# Close_eMuff.net
KiCad netlist of a schematic drawn in EAGLE
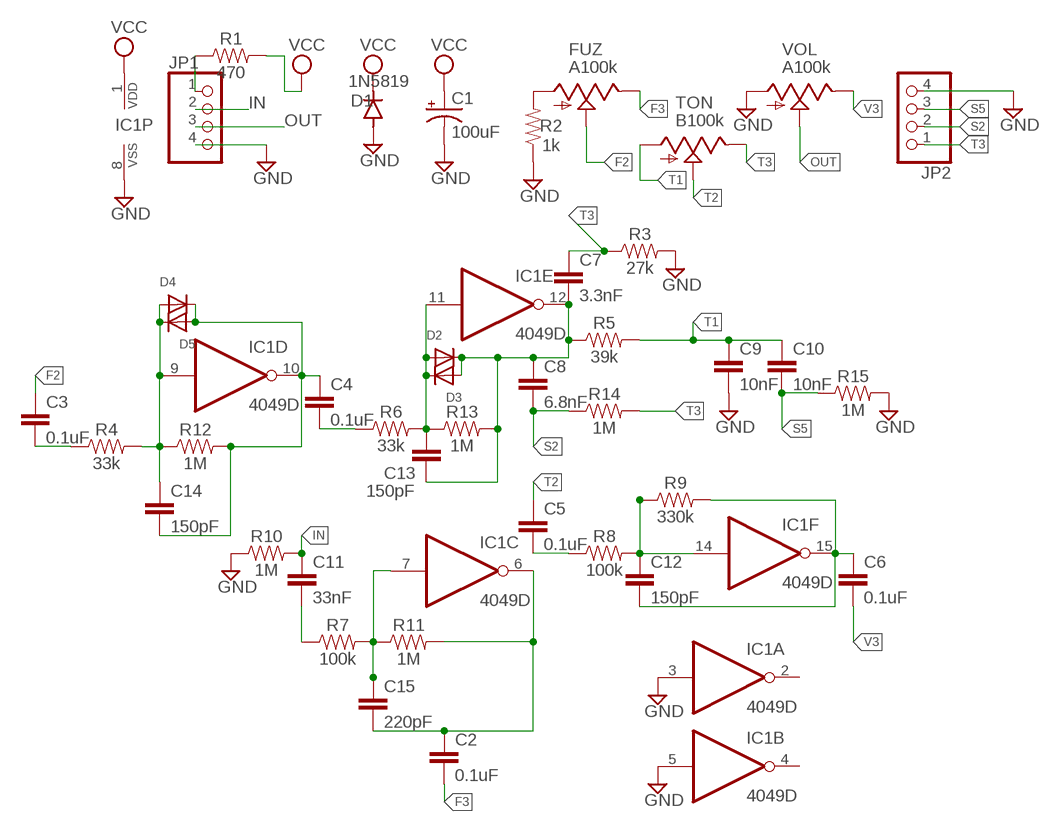
[diagram p0: schematic, sheet 1]

(export (version "E")
  (design (tool "Eeschema 10.0.6"))
  (components
    (comp (ref "C1")
      (value "100uF")
      (footprint "eagle-import:PAN_B_SMD+THRU")
      (libsource (lib "eagle-import") (part "CAP_SMD+THRUPAN_B"))
    )
    (comp (ref "C2")
      (value "0.1uF")
      (footprint "eagle-import:0603")
      (libsource (lib "eagle-import") (part "0.1UF-0603-25V-(+80/-20%)"))
    )
    (comp (ref "C3")
      (value "0.1uF")
      (footprint "eagle-import:0603")
      (libsource (lib "eagle-import") (part "0.1UF-0603-25V-(+80/-20%)"))
    )
    (comp (ref "C4")
      (value "0.1uF")
      (footprint "eagle-import:0603")
      (libsource (lib "eagle-import") (part "0.1UF-0603-25V-(+80/-20%)"))
    )
    (comp (ref "C5")
      (value "0.1uF")
      (footprint "eagle-import:0603")
      (libsource (lib "eagle-import") (part "0.1UF-0603-25V-(+80/-20%)"))
    )
    (comp (ref "C6")
      (value "0.1uF")
      (footprint "eagle-import:0603")
      (libsource (lib "eagle-import") (part "0.1UF-0603-25V-(+80/-20%)"))
    )
    (comp (ref "C7")
      (value "3.3nF")
      (footprint "eagle-import:0603")
      (libsource (lib "eagle-import") (part "3.3NF-0603-100V-10%"))
    )
    (comp (ref "C8")
      (value "6.8nF")
      (footprint "eagle-import:0603")
      (libsource (lib "eagle-import") (part "3.3NF-0603-100V-10%"))
    )
    (comp (ref "C9")
      (value "10nF")
      (footprint "eagle-import:0603")
      (libsource (lib "eagle-import") (part "10NF-0603-50V-10%"))
    )
    (comp (ref "C10")
      (value "10nF")
      (footprint "eagle-import:0603")
      (libsource (lib "eagle-import") (part "10NF-0603-50V-10%"))
    )
    (comp (ref "C11")
      (value "33nF")
      (footprint "eagle-import:0603")
      (libsource (lib "eagle-import") (part "33PF-0603-50V-5%"))
    )
    (comp (ref "C12")
      (value "150pF")
      (footprint "eagle-import:0603")
      (libsource (lib "eagle-import") (part "180PF-0603-50V-5%"))
    )
    (comp (ref "C13")
      (value "150pF")
      (footprint "eagle-import:0603")
      (libsource (lib "eagle-import") (part "180PF-0603-50V-5%"))
    )
    (comp (ref "C14")
      (value "150pF")
      (footprint "eagle-import:0603")
      (libsource (lib "eagle-import") (part "180PF-0603-50V-5%"))
    )
    (comp (ref "C15")
      (value "220pF")
      (footprint "eagle-import:0603")
      (libsource (lib "eagle-import") (part "270PF-0603-50V-5%"))
    )
    (comp (ref "D1")
      (value "1N5819")
      (footprint "eagle-import:SOD123")
      (libsource (lib "eagle-import") (part "DIODE-SOD123"))
    )
    (comp (ref "D2")
      (value "DIODESOD-123")
      (footprint "eagle-import:SOD-123")
      (libsource (lib "eagle-import") (part "DIODESOD-123"))
    )
    (comp (ref "D3")
      (value "DIODESOD-123")
      (footprint "eagle-import:SOD-123")
      (libsource (lib "eagle-import") (part "DIODESOD-123"))
    )
    (comp (ref "D4")
      (value "DIODESOD-123")
      (footprint "eagle-import:SOD-123")
      (libsource (lib "eagle-import") (part "DIODESOD-123"))
    )
    (comp (ref "D5")
      (value "DIODESOD-123")
      (footprint "eagle-import:SOD-123")
      (libsource (lib "eagle-import") (part "DIODESOD-123"))
    )
    (comp (ref "FUZ")
      (value "A100k")
      (footprint "eagle-import:9MM_SNAP-IN_POT")
      (libsource (lib "eagle-import") (part "9MM_SNAP-IN_POT_"))
    )
    (comp (ref "IC1")
      (value "4049D")
      (footprint "eagle-import:SO16")
      (libsource (lib "eagle-import") (part "4049D"))
    )
    (comp (ref "JP1")
      (value "PINHD-1X4")
      (footprint "eagle-import:1X04")
      (libsource (lib "eagle-import") (part "PINHD-1X4"))
    )
    (comp (ref "JP2")
      (value "PINHD-1X4")
      (footprint "eagle-import:1X04")
      (libsource (lib "eagle-import") (part "pinhead_325_PINHD-1X4"))
    )
    (comp (ref "R1")
      (value "470")
      (footprint "eagle-import:0603")
      (libsource (lib "eagle-import") (part "470OHM-0603-1/10W-1%"))
    )
    (comp (ref "R2")
      (value "1k")
      (footprint "eagle-import:0603")
      (libsource (lib "eagle-import") (part "1KOHM-0603-1/10W-1%"))
    )
    (comp (ref "R3")
      (value "27k")
      (footprint "eagle-import:0603")
      (libsource (lib "eagle-import") (part "27OHM-0603-1/10W-1%"))
    )
    (comp (ref "R4")
      (value "33k")
      (footprint "eagle-import:0603")
      (libsource (lib "eagle-import") (part "33KOHM-0603-1/10W-1%"))
    )
    (comp (ref "R5")
      (value "39k")
      (footprint "eagle-import:0603")
      (libsource (lib "eagle-import") (part "39KOHM-0603-1/10W-1%"))
    )
    (comp (ref "R6")
      (value "33k")
      (footprint "eagle-import:0603")
      (libsource (lib "eagle-import") (part "33KOHM-0603-1/10W-1%"))
    )
    (comp (ref "R7")
      (value "100k")
      (footprint "eagle-import:0603")
      (libsource (lib "eagle-import") (part "100KOHM-0603-1/10W-1%"))
    )
    (comp (ref "R8")
      (value "100k")
      (footprint "eagle-import:0603")
      (libsource (lib "eagle-import") (part "100KOHM-0603-1/10W-1%"))
    )
    (comp (ref "R9")
      (value "330k")
      (footprint "eagle-import:0603")
      (libsource (lib "eagle-import") (part "330KOHM-0603-1/10W-1%"))
    )
    (comp (ref "R10")
      (value "1M")
      (footprint "eagle-import:0603")
      (libsource (lib "eagle-import") (part "1MOHM-0603-1/4W-5%"))
    )
    (comp (ref "R11")
      (value "1M")
      (footprint "eagle-import:0603")
      (libsource (lib "eagle-import") (part "1MOHM-0603-1/4W-5%"))
    )
    (comp (ref "R12")
      (value "1M")
      (footprint "eagle-import:0603")
      (libsource (lib "eagle-import") (part "1MOHM-0603-1/4W-5%"))
    )
    (comp (ref "R13")
      (value "1M")
      (footprint "eagle-import:0603")
      (libsource (lib "eagle-import") (part "1MOHM-0603-1/4W-5%"))
    )
    (comp (ref "R14")
      (value "1M")
      (footprint "eagle-import:0603")
      (libsource (lib "eagle-import") (part "1MOHM-0603-1/4W-5%"))
    )
    (comp (ref "R15")
      (value "1M")
      (footprint "eagle-import:0603")
      (libsource (lib "eagle-import") (part "1MOHM-0603-1/4W-5%"))
    )
    (comp (ref "TON")
      (value "B100k")
      (footprint "eagle-import:9MM_SNAP-IN_POT")
      (libsource (lib "eagle-import") (part "9MM_SNAP-IN_POT_"))
    )
    (comp (ref "VOL")
      (value "A100k")
      (footprint "eagle-import:9MM_SNAP-IN_POT")
      (libsource (lib "eagle-import") (part "9MM_SNAP-IN_POT_"))
    )
  )
  (nets
    (net (code "1") (name "F2") (class "Default")
      (node (ref "C3") (pin "1") (pinfunction "1_1") (pintype "passive"))
      (node (ref "FUZ") (pin "2") (pinfunction "S_2") (pintype "passive"))
    )
    (net (code "2") (name "F3") (class "Default")
      (node (ref "C2") (pin "2") (pinfunction "2_2") (pintype "passive"))
      (node (ref "FUZ") (pin "3") (pinfunction "E_3") (pintype "passive"))
    )
    (net (code "3") (name "GND") (class "Default")
      (node (ref "C1") (pin "-") (pinfunction "-_-") (pintype "passive"))
      (node (ref "C1") (pin "--") (pinfunction "-_--") (pintype "passive"))
      (node (ref "C9") (pin "2") (pinfunction "2_2") (pintype "passive"))
      (node (ref "D1") (pin "A") (pinfunction "A_A") (pintype "passive"))
      (node (ref "IC1") (pin "3") (pinfunction "I_3") (pintype "input"))
      (node (ref "IC1") (pin "5") (pinfunction "I_5") (pintype "input"))
      (node (ref "IC1") (pin "8") (pinfunction "VSS_8") (pintype "power_in"))
      (node (ref "JP1") (pin "4") (pinfunction "4_4") (pintype "passive"))
      (node (ref "JP2") (pin "4") (pinfunction "4_4") (pintype "passive"))
      (node (ref "R10") (pin "1") (pinfunction "1_1") (pintype "passive"))
      (node (ref "R15") (pin "2") (pinfunction "2_2") (pintype "passive"))
      (node (ref "R2") (pin "1") (pinfunction "1_1") (pintype "passive"))
      (node (ref "R3") (pin "2") (pinfunction "2_2") (pintype "passive"))
      (node (ref "VOL") (pin "1") (pinfunction "A_1") (pintype "passive"))
    )
    (net (code "4") (name "IN") (class "Default")
      (node (ref "C11") (pin "1") (pinfunction "1_1") (pintype "passive"))
      (node (ref "JP1") (pin "2") (pinfunction "2_2") (pintype "passive"))
      (node (ref "R10") (pin "2") (pinfunction "2_2") (pintype "passive"))
    )
    (net (code "5") (name "Net-(C3-Pad2)") (class "Default")
      (node (ref "C3") (pin "2") (pinfunction "2_2") (pintype "passive"))
      (node (ref "R4") (pin "1") (pinfunction "1_1") (pintype "passive"))
    )
    (net (code "6") (name "Net-(C4-Pad2)") (class "Default")
      (node (ref "C4") (pin "2") (pinfunction "2_2") (pintype "passive"))
      (node (ref "R6") (pin "1") (pinfunction "1_1") (pintype "passive"))
    )
    (net (code "7") (name "Net-(C5-Pad2)") (class "Default")
      (node (ref "C5") (pin "2") (pinfunction "2_2") (pintype "passive"))
      (node (ref "R8") (pin "1") (pinfunction "1_1") (pintype "passive"))
    )
    (net (code "8") (name "Net-(C11-Pad2)") (class "Default")
      (node (ref "C11") (pin "2") (pinfunction "2_2") (pintype "passive"))
      (node (ref "R7") (pin "1") (pinfunction "1_1") (pintype "passive"))
    )
    (net (code "9") (name "Net-(FUZ-A)") (class "Default")
      (node (ref "FUZ") (pin "1") (pinfunction "A_1") (pintype "passive"))
      (node (ref "R2") (pin "2") (pinfunction "2_2") (pintype "passive"))
    )
    (net (code "10") (name "Net-(IC1C-I)") (class "Default")
      (node (ref "C15") (pin "1") (pinfunction "1_1") (pintype "passive"))
      (node (ref "IC1") (pin "7") (pinfunction "I_7") (pintype "input"))
      (node (ref "R11") (pin "1") (pinfunction "1_1") (pintype "passive"))
      (node (ref "R7") (pin "2") (pinfunction "2_2") (pintype "passive"))
    )
    (net (code "11") (name "Net-(IC1C-O)") (class "Default")
      (node (ref "C15") (pin "2") (pinfunction "2_2") (pintype "passive"))
      (node (ref "C2") (pin "1") (pinfunction "1_1") (pintype "passive"))
      (node (ref "IC1") (pin "6") (pinfunction "O_6") (pintype "output"))
      (node (ref "R11") (pin "2") (pinfunction "2_2") (pintype "passive"))
    )
    (net (code "12") (name "Net-(IC1D-I)") (class "Default")
      (node (ref "C14") (pin "1") (pinfunction "1_1") (pintype "passive"))
      (node (ref "D4") (pin "A") (pinfunction "A_A") (pintype "passive"))
      (node (ref "D5") (pin "C") (pinfunction "C_C") (pintype "passive"))
      (node (ref "IC1") (pin "9") (pinfunction "I_9") (pintype "input"))
      (node (ref "R12") (pin "1") (pinfunction "1_1") (pintype "passive"))
      (node (ref "R4") (pin "2") (pinfunction "2_2") (pintype "passive"))
    )
    (net (code "13") (name "Net-(IC1D-O)") (class "Default")
      (node (ref "C14") (pin "2") (pinfunction "2_2") (pintype "passive"))
      (node (ref "C4") (pin "1") (pinfunction "1_1") (pintype "passive"))
      (node (ref "D4") (pin "C") (pinfunction "C_C") (pintype "passive"))
      (node (ref "D5") (pin "A") (pinfunction "A_A") (pintype "passive"))
      (node (ref "IC1") (pin "10") (pinfunction "O_10") (pintype "output"))
      (node (ref "R12") (pin "2") (pinfunction "2_2") (pintype "passive"))
    )
    (net (code "14") (name "Net-(IC1E-I)") (class "Default")
      (node (ref "C13") (pin "1") (pinfunction "1_1") (pintype "passive"))
      (node (ref "D2") (pin "A") (pinfunction "A_A") (pintype "passive"))
      (node (ref "D3") (pin "C") (pinfunction "C_C") (pintype "passive"))
      (node (ref "IC1") (pin "11") (pinfunction "I_11") (pintype "input"))
      (node (ref "R13") (pin "1") (pinfunction "1_1") (pintype "passive"))
      (node (ref "R6") (pin "2") (pinfunction "2_2") (pintype "passive"))
    )
    (net (code "15") (name "Net-(IC1E-O)") (class "Default")
      (node (ref "C13") (pin "2") (pinfunction "2_2") (pintype "passive"))
      (node (ref "C7") (pin "2") (pinfunction "2_2") (pintype "passive"))
      (node (ref "C8") (pin "1") (pinfunction "1_1") (pintype "passive"))
      (node (ref "D2") (pin "C") (pinfunction "C_C") (pintype "passive"))
      (node (ref "D3") (pin "A") (pinfunction "A_A") (pintype "passive"))
      (node (ref "IC1") (pin "12") (pinfunction "O_12") (pintype "output"))
      (node (ref "R13") (pin "2") (pinfunction "2_2") (pintype "passive"))
      (node (ref "R5") (pin "1") (pinfunction "1_1") (pintype "passive"))
    )
    (net (code "16") (name "Net-(IC1F-I)") (class "Default")
      (node (ref "C12") (pin "1") (pinfunction "1_1") (pintype "passive"))
      (node (ref "IC1") (pin "14") (pinfunction "I_14") (pintype "input"))
      (node (ref "R8") (pin "2") (pinfunction "2_2") (pintype "passive"))
      (node (ref "R9") (pin "1") (pinfunction "1_1") (pintype "passive"))
    )
    (net (code "17") (name "Net-(IC1F-O)") (class "Default")
      (node (ref "C12") (pin "2") (pinfunction "2_2") (pintype "passive"))
      (node (ref "C6") (pin "1") (pinfunction "1_1") (pintype "passive"))
      (node (ref "IC1") (pin "15") (pinfunction "O_15") (pintype "output"))
      (node (ref "R9") (pin "2") (pinfunction "2_2") (pintype "passive"))
    )
    (net (code "18") (name "Net-(JP1-Pad1)") (class "Default")
      (node (ref "JP1") (pin "1") (pinfunction "1_1") (pintype "passive"))
      (node (ref "R1") (pin "1") (pinfunction "1_1") (pintype "passive"))
    )
    (net (code "19") (name "OUT") (class "Default")
      (node (ref "JP1") (pin "3") (pinfunction "3_3") (pintype "passive"))
      (node (ref "VOL") (pin "2") (pinfunction "S_2") (pintype "passive"))
    )
    (net (code "20") (name "S2") (class "Default")
      (node (ref "C8") (pin "2") (pinfunction "2_2") (pintype "passive"))
      (node (ref "JP2") (pin "2") (pinfunction "2_2") (pintype "passive"))
      (node (ref "R14") (pin "1") (pinfunction "1_1") (pintype "passive"))
    )
    (net (code "21") (name "S5") (class "Default")
      (node (ref "C10") (pin "2") (pinfunction "2_2") (pintype "passive"))
      (node (ref "JP2") (pin "3") (pinfunction "3_3") (pintype "passive"))
      (node (ref "R15") (pin "1") (pinfunction "1_1") (pintype "passive"))
    )
    (net (code "22") (name "T1") (class "Default")
      (node (ref "C10") (pin "1") (pinfunction "1_1") (pintype "passive"))
      (node (ref "C9") (pin "1") (pinfunction "1_1") (pintype "passive"))
      (node (ref "R5") (pin "2") (pinfunction "2_2") (pintype "passive"))
      (node (ref "TON") (pin "1") (pinfunction "A_1") (pintype "passive"))
    )
    (net (code "23") (name "T2") (class "Default")
      (node (ref "C5") (pin "1") (pinfunction "1_1") (pintype "passive"))
      (node (ref "TON") (pin "2") (pinfunction "S_2") (pintype "passive"))
    )
    (net (code "24") (name "T3") (class "Default")
      (node (ref "C7") (pin "1") (pinfunction "1_1") (pintype "passive"))
      (node (ref "JP2") (pin "1") (pinfunction "1_1") (pintype "passive"))
      (node (ref "R14") (pin "2") (pinfunction "2_2") (pintype "passive"))
      (node (ref "R3") (pin "1") (pinfunction "1_1") (pintype "passive"))
      (node (ref "TON") (pin "3") (pinfunction "E_3") (pintype "passive"))
    )
    (net (code "25") (name "V3") (class "Default")
      (node (ref "C6") (pin "2") (pinfunction "2_2") (pintype "passive"))
      (node (ref "VOL") (pin "3") (pinfunction "E_3") (pintype "passive"))
    )
    (net (code "26") (name "VCC") (class "Default")
      (node (ref "C1") (pin "+") (pinfunction "+_+") (pintype "passive"))
      (node (ref "C1") (pin "++") (pinfunction "+_++") (pintype "passive"))
      (node (ref "D1") (pin "C") (pinfunction "C_C") (pintype "passive"))
      (node (ref "IC1") (pin "1") (pinfunction "VDD_1") (pintype "power_in"))
      (node (ref "R1") (pin "2") (pinfunction "2_2") (pintype "passive"))
    )
    (net (code "27") (name "unconnected-(IC1A-O-Pad2)") (class "Default")
      (node (ref "IC1") (pin "2") (pinfunction "O_2") (pintype "output"))
    )
    (net (code "28") (name "unconnected-(IC1B-O-Pad4)") (class "Default")
      (node (ref "IC1") (pin "4") (pinfunction "O_4") (pintype "output"))
    )
  )
)
